# rev1_v1.net
KiCad netlist of a schematic drawn in EAGLE
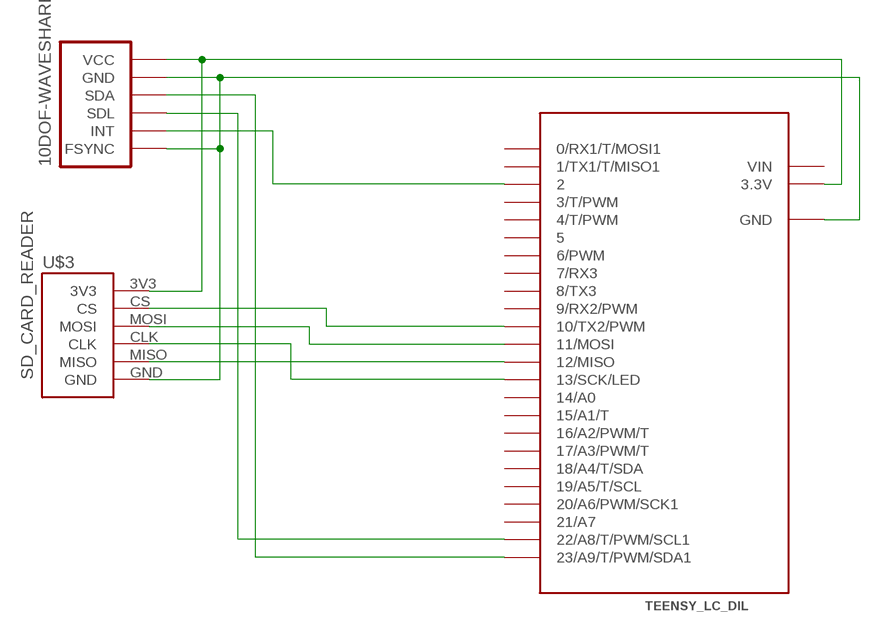
[diagram p0: schematic, sheet 1]

(export (version "E")
  (design (tool "Eeschema 10.0.6"))
  (components
    (comp (ref "U$1")
      (value "TEENSY_LC_DIL")
      (footprint "eagle-import:TEENSY_3.0-3.2&LC_DIL")
      (libsource (lib "eagle-import") (part "TEENSY_LC_DIL"))
    )
    (comp (ref "U$2")
      (value "10DOF-WAVESHARE")
      (footprint "eagle-import:10DOF-WAVESHARE")
      (libsource (lib "eagle-import") (part "10DOF-WAVESHARE"))
    )
    (comp (ref "U$3")
      (value "SD_CARD_READER")
      (footprint "eagle-import:MICRO_SD_READER_3V3")
      (libsource (lib "eagle-import") (part "SD_CARD_READER"))
    )
  )
  (nets
    (net (code "1") (name "/VIN") (class "Default")
      (node (ref "U$1") (pin "VIN") (pinfunction "VIN_VIN") (pintype "power_in"))
    )
    (net (code "2") (name "Net-(U$1-10{slash}TX2{slash}PWM)") (class "Default")
      (node (ref "U$1") (pin "10") (pinfunction "10/TX2/PWM_10") (pintype "bidirectional"))
      (node (ref "U$3") (pin "CS") (pinfunction "CS_CS") (pintype "bidirectional"))
    )
    (net (code "3") (name "Net-(U$1-11{slash}MOSI)") (class "Default")
      (node (ref "U$1") (pin "11") (pinfunction "11/MOSI_11") (pintype "bidirectional"))
      (node (ref "U$3") (pin "MOSI") (pinfunction "MOSI_MOSI") (pintype "bidirectional"))
    )
    (net (code "4") (name "Net-(U$1-12{slash}MISO)") (class "Default")
      (node (ref "U$1") (pin "12") (pinfunction "12/MISO_12") (pintype "bidirectional"))
      (node (ref "U$3") (pin "MISO") (pinfunction "MISO_MISO") (pintype "bidirectional"))
    )
    (net (code "5") (name "Net-(U$1-13{slash}SCK{slash}LED)") (class "Default")
      (node (ref "U$1") (pin "13") (pinfunction "13/SCK/LED_13") (pintype "bidirectional"))
      (node (ref "U$3") (pin "CLK") (pinfunction "CLK_CLK") (pintype "bidirectional"))
    )
    (net (code "6") (name "Net-(U$1-22{slash}A8{slash}T{slash}PWM{slash}SCL1)") (class "Default")
      (node (ref "U$1") (pin "22/A8") (pinfunction "22/A8/T/PWM/SCL1_22/A8") (pintype "bidirectional"))
      (node (ref "U$2") (pin "SCL") (pinfunction "SDL_SCL") (pintype "passive"))
    )
    (net (code "7") (name "Net-(U$1-23{slash}A9{slash}T{slash}PWM{slash}SDA1)") (class "Default")
      (node (ref "U$1") (pin "23/A9") (pinfunction "23/A9/T/PWM/SDA1_23/A9") (pintype "bidirectional"))
      (node (ref "U$2") (pin "SDA") (pinfunction "SDA_SDA") (pintype "passive"))
    )
    (net (code "8") (name "Net-(U$1-GND-PadAGND)") (class "Default")
      (node (ref "U$1") (pin "AGND") (pinfunction "GND_AGND") (pintype "power_in"))
      (node (ref "U$1") (pin "GND") (pinfunction "GND_GND") (pintype "power_in"))
      (node (ref "U$2") (pin "FSYNC") (pinfunction "FSYNC_FSYNC") (pintype "passive"))
      (node (ref "U$2") (pin "GND") (pinfunction "GND_GND") (pintype "passive"))
      (node (ref "U$3") (pin "GND") (pinfunction "GND_GND") (pintype "bidirectional"))
    )
    (net (code "9") (name "Net-(U$1-Pad2)") (class "Default")
      (node (ref "U$1") (pin "2") (pinfunction "2_2") (pintype "bidirectional"))
      (node (ref "U$2") (pin "INT") (pinfunction "INT_INT") (pintype "passive"))
    )
    (net (code "10") (name "Net-(U$1-Pad3.3V)") (class "Default")
      (node (ref "U$1") (pin "3.3V") (pinfunction "3.3V_3.3V") (pintype "power_in"))
      (node (ref "U$2") (pin "VCC") (pinfunction "VCC_VCC") (pintype "passive"))
      (node (ref "U$3") (pin "3V3") (pinfunction "3V3_3V3") (pintype "bidirectional"))
    )
    (net (code "11") (name "unconnected-(U$1-0{slash}RX1{slash}T{slash}MOSI1-Pad0)") (class "Default")
      (node (ref "U$1") (pin "0") (pinfunction "0/RX1/T/MOSI1_0") (pintype "bidirectional"))
    )
    (net (code "12") (name "unconnected-(U$1-1{slash}TX1{slash}T{slash}MISO1-Pad1)") (class "Default")
      (node (ref "U$1") (pin "1") (pinfunction "1/TX1/T/MISO1_1") (pintype "bidirectional"))
    )
    (net (code "13") (name "unconnected-(U$1-3{slash}T{slash}PWM-Pad3)") (class "Default")
      (node (ref "U$1") (pin "3") (pinfunction "3/T/PWM_3") (pintype "bidirectional"))
    )
    (net (code "14") (name "unconnected-(U$1-4{slash}T{slash}PWM-Pad4)") (class "Default")
      (node (ref "U$1") (pin "4") (pinfunction "4/T/PWM_4") (pintype "bidirectional"))
    )
    (net (code "15") (name "unconnected-(U$1-6{slash}PWM-Pad6)") (class "Default")
      (node (ref "U$1") (pin "6") (pinfunction "6/PWM_6") (pintype "bidirectional"))
    )
    (net (code "16") (name "unconnected-(U$1-7{slash}RX3-Pad7)") (class "Default")
      (node (ref "U$1") (pin "7") (pinfunction "7/RX3_7") (pintype "bidirectional"))
    )
    (net (code "17") (name "unconnected-(U$1-8{slash}TX3-Pad8)") (class "Default")
      (node (ref "U$1") (pin "8") (pinfunction "8/TX3_8") (pintype "bidirectional"))
    )
    (net (code "18") (name "unconnected-(U$1-9{slash}RX2{slash}PWM-Pad9)") (class "Default")
      (node (ref "U$1") (pin "9") (pinfunction "9/RX2/PWM_9") (pintype "bidirectional"))
    )
    (net (code "19") (name "unconnected-(U$1-15{slash}A1{slash}T-Pad15{slash}A1)") (class "Default")
      (node (ref "U$1") (pin "15/A1") (pinfunction "15/A1/T_15/A1") (pintype "bidirectional"))
    )
    (net (code "20") (name "unconnected-(U$1-16{slash}A2{slash}PWM{slash}T-Pad16{slash}A2)") (class "Default")
      (node (ref "U$1") (pin "16/A2") (pinfunction "16/A2/PWM/T_16/A2") (pintype "bidirectional"))
    )
    (net (code "21") (name "unconnected-(U$1-17{slash}A3{slash}PWM{slash}T-Pad17{slash}A3)") (class "Default")
      (node (ref "U$1") (pin "17/A3") (pinfunction "17/A3/PWM/T_17/A3") (pintype "bidirectional"))
    )
    (net (code "22") (name "unconnected-(U$1-18{slash}A4{slash}T{slash}SDA-Pad18{slash}A4)") (class "Default")
      (node (ref "U$1") (pin "18/A4") (pinfunction "18/A4/T/SDA_18/A4") (pintype "bidirectional"))
    )
    (net (code "23") (name "unconnected-(U$1-19{slash}A5{slash}T{slash}SCL-Pad19{slash}A5)") (class "Default")
      (node (ref "U$1") (pin "19/A5") (pinfunction "19/A5/T/SCL_19/A5") (pintype "bidirectional"))
    )
    (net (code "24") (name "unconnected-(U$1-20{slash}A6{slash}PWM{slash}SCK1-Pad20{slash}A6)") (class "Default")
      (node (ref "U$1") (pin "20/A6") (pinfunction "20/A6/PWM/SCK1_20/A6") (pintype "bidirectional"))
    )
    (net (code "25") (name "unconnected-(U$1-Pad5)") (class "Default")
      (node (ref "U$1") (pin "5") (pinfunction "5_5") (pintype "bidirectional"))
    )
    (net (code "26") (name "unconnected-(U$1-Pad14{slash}A0)") (class "Default")
      (node (ref "U$1") (pin "14/A0") (pinfunction "14/A0_14/A0") (pintype "bidirectional"))
    )
    (net (code "27") (name "unconnected-(U$1-Pad21{slash}A7)") (class "Default")
      (node (ref "U$1") (pin "21/A7") (pinfunction "21/A7_21/A7") (pintype "bidirectional"))
    )
  )
)
